# SCH_task3_2026-04-27.net
KiCad netlist of a schematic drawn in EasyEDA
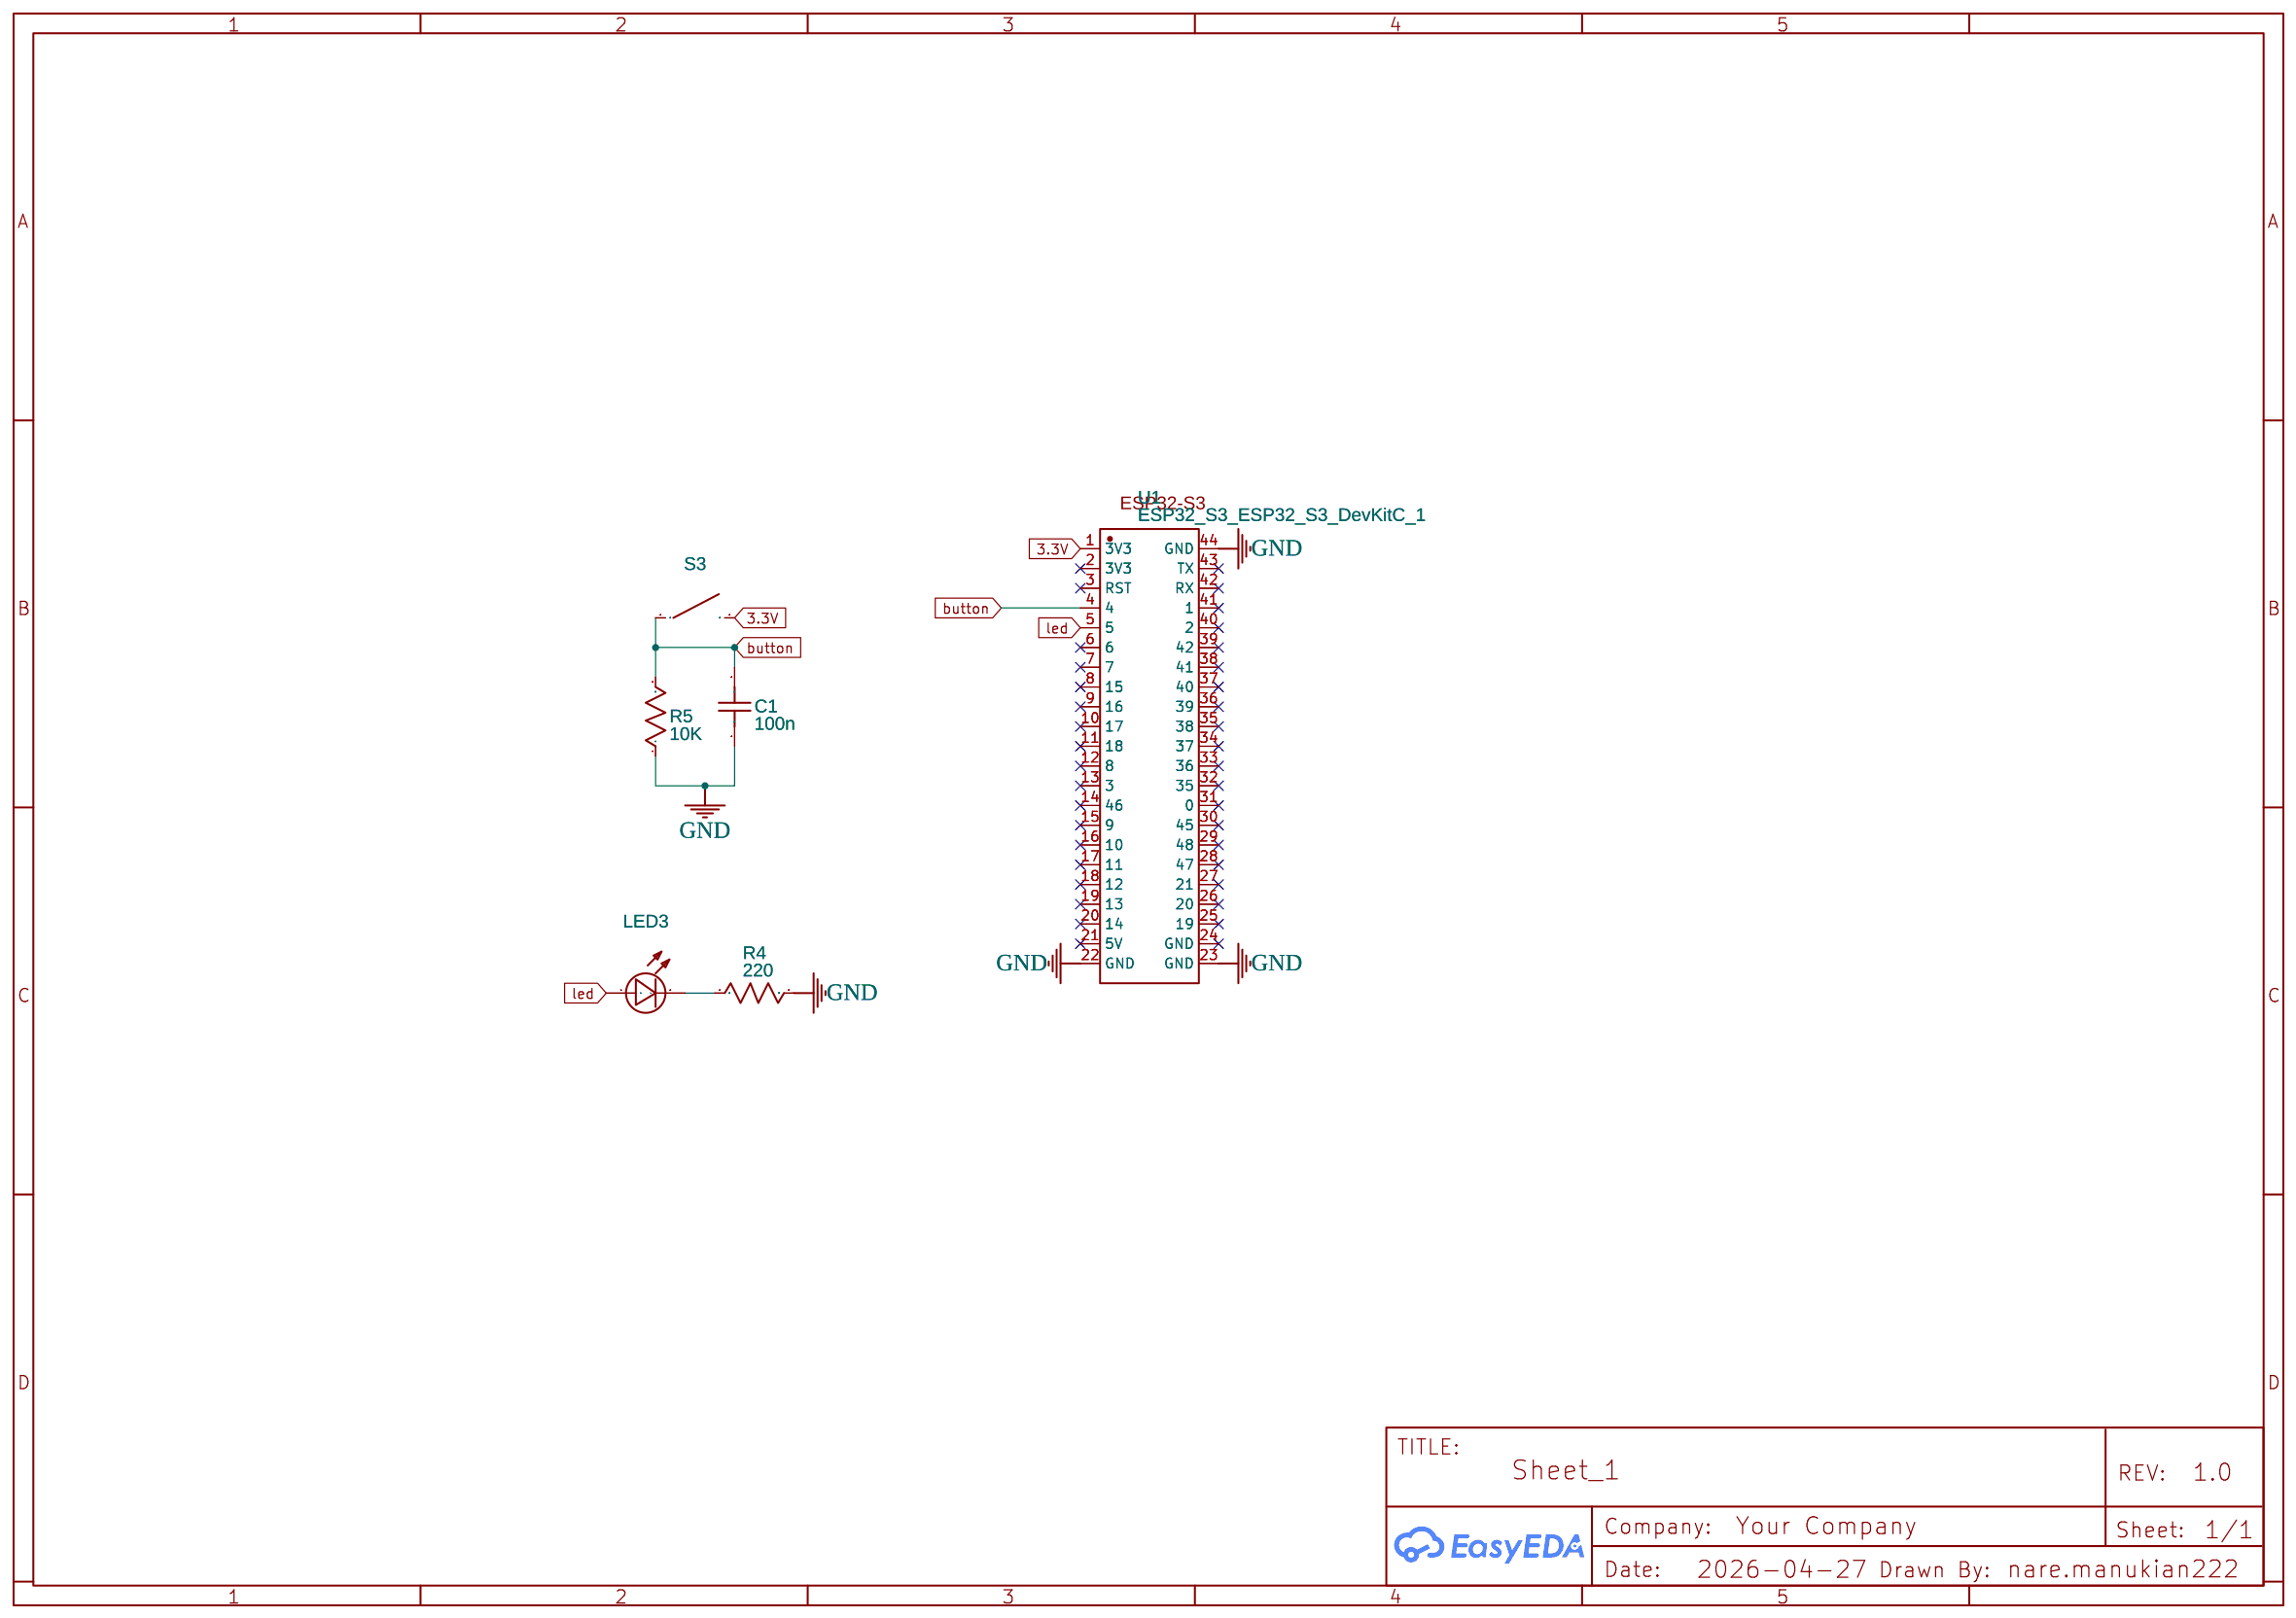
[diagram p0: schematic sheet]

(export (version "E")
  (design (tool "Eeschema 10.0.6"))
  (components
    (comp (ref "C1") (value "100n") (libsource (lib "") (part "Capacitor_US")))
    (comp (ref "LED3") (value "LED") (libsource (lib "") (part "LED")))
    (comp (ref "R4") (value "220") (libsource (lib "") (part "Resistor_US")))
    (comp (ref "R5") (value "10K") (libsource (lib "") (part "Resistor_US_1")))
    (comp (ref "S3") (value "SPST_Open") (libsource (lib "") (part "SPST")))
    (comp (ref "U1")
      (value "ESP32_S3_ESP32_S3_DevKitC_1")
      (fields (field (name "Manufacturer") "DUBEUYEW"))
      (libsource (lib "") (part "ESP32_S3_ESP32_S3_DevKitC_1"))
    )
  )
  (nets
    (net (code "1") (name "3.3V") (class "Default")
      (node (ref "S3") (pin "2") (pinfunction "2_2") (pintype "unspecified"))
      (node (ref "U1") (pin "1") (pinfunction "3V3_1") (pintype "unspecified"))
    )
    (net (code "2") (name "GND") (class "Default")
      (node (ref "C1") (pin "1") (pinfunction "1_1") (pintype "unspecified"))
      (node (ref "R4") (pin "2") (pinfunction "2_2") (pintype "unspecified"))
      (node (ref "R5") (pin "1") (pinfunction "1_1") (pintype "unspecified"))
      (node (ref "U1") (pin "22") (pinfunction "GND_22") (pintype "unspecified"))
      (node (ref "U1") (pin "23") (pinfunction "GND_23") (pintype "unspecified"))
      (node (ref "U1") (pin "44") (pinfunction "GND_44") (pintype "unspecified"))
    )
    (net (code "3") (name "Net-(LED3--)") (class "Default")
      (node (ref "LED3") (pin "2") (pinfunction "-_2") (pintype "unspecified"))
      (node (ref "R4") (pin "1") (pinfunction "1_1") (pintype "unspecified"))
    )
    (net (code "4") (name "button") (class "Default")
      (node (ref "C1") (pin "2") (pinfunction "2_2") (pintype "unspecified"))
      (node (ref "R5") (pin "2") (pinfunction "2_2") (pintype "unspecified"))
      (node (ref "S3") (pin "1") (pinfunction "1_1") (pintype "unspecified"))
      (node (ref "U1") (pin "4") (pinfunction "4_4") (pintype "unspecified"))
    )
    (net (code "5") (name "led") (class "Default")
      (node (ref "LED3") (pin "1") (pinfunction "+_1") (pintype "unspecified"))
      (node (ref "U1") (pin "5") (pinfunction "5_5") (pintype "unspecified"))
    )
    (net (code "6") (name "unconnected-(U1-0-Pad31)") (class "Default")
      (node (ref "U1") (pin "31") (pinfunction "0_31") (pintype "unspecified+no_connect"))
    )
    (net (code "7") (name "unconnected-(U1-1-Pad41)") (class "Default")
      (node (ref "U1") (pin "41") (pinfunction "1_41") (pintype "unspecified+no_connect"))
    )
    (net (code "8") (name "unconnected-(U1-2-Pad40)") (class "Default")
      (node (ref "U1") (pin "40") (pinfunction "2_40") (pintype "unspecified+no_connect"))
    )
    (net (code "9") (name "unconnected-(U1-3-Pad13)") (class "Default")
      (node (ref "U1") (pin "13") (pinfunction "3_13") (pintype "unspecified+no_connect"))
    )
    (net (code "10") (name "unconnected-(U1-3V3-Pad2)") (class "Default")
      (node (ref "U1") (pin "2") (pinfunction "3V3_2") (pintype "unspecified+no_connect"))
    )
    (net (code "11") (name "unconnected-(U1-5V-Pad21)") (class "Default")
      (node (ref "U1") (pin "21") (pinfunction "5V_21") (pintype "unspecified+no_connect"))
    )
    (net (code "12") (name "unconnected-(U1-8-Pad12)") (class "Default")
      (node (ref "U1") (pin "12") (pinfunction "8_12") (pintype "unspecified+no_connect"))
    )
    (net (code "13") (name "unconnected-(U1-9-Pad15)") (class "Default")
      (node (ref "U1") (pin "15") (pinfunction "9_15") (pintype "unspecified+no_connect"))
    )
    (net (code "14") (name "unconnected-(U1-10-Pad16)") (class "Default")
      (node (ref "U1") (pin "16") (pinfunction "10_16") (pintype "unspecified+no_connect"))
    )
    (net (code "15") (name "unconnected-(U1-11-Pad17)") (class "Default")
      (node (ref "U1") (pin "17") (pinfunction "11_17") (pintype "unspecified+no_connect"))
    )
    (net (code "16") (name "unconnected-(U1-12-Pad18)") (class "Default")
      (node (ref "U1") (pin "18") (pinfunction "12_18") (pintype "unspecified+no_connect"))
    )
    (net (code "17") (name "unconnected-(U1-13-Pad19)") (class "Default")
      (node (ref "U1") (pin "19") (pinfunction "13_19") (pintype "unspecified+no_connect"))
    )
    (net (code "18") (name "unconnected-(U1-14-Pad20)") (class "Default")
      (node (ref "U1") (pin "20") (pinfunction "14_20") (pintype "unspecified+no_connect"))
    )
    (net (code "19") (name "unconnected-(U1-15-Pad8)") (class "Default")
      (node (ref "U1") (pin "8") (pinfunction "15_8") (pintype "unspecified+no_connect"))
    )
    (net (code "20") (name "unconnected-(U1-16-Pad9)") (class "Default")
      (node (ref "U1") (pin "9") (pinfunction "16_9") (pintype "unspecified+no_connect"))
    )
    (net (code "21") (name "unconnected-(U1-17-Pad10)") (class "Default")
      (node (ref "U1") (pin "10") (pinfunction "17_10") (pintype "unspecified+no_connect"))
    )
    (net (code "22") (name "unconnected-(U1-18-Pad11)") (class "Default")
      (node (ref "U1") (pin "11") (pinfunction "18_11") (pintype "unspecified+no_connect"))
    )
    (net (code "23") (name "unconnected-(U1-19-Pad25)") (class "Default")
      (node (ref "U1") (pin "25") (pinfunction "19_25") (pintype "unspecified+no_connect"))
    )
    (net (code "24") (name "unconnected-(U1-20-Pad26)") (class "Default")
      (node (ref "U1") (pin "26") (pinfunction "20_26") (pintype "unspecified+no_connect"))
    )
    (net (code "25") (name "unconnected-(U1-21-Pad27)") (class "Default")
      (node (ref "U1") (pin "27") (pinfunction "21_27") (pintype "unspecified+no_connect"))
    )
    (net (code "26") (name "unconnected-(U1-35-Pad32)") (class "Default")
      (node (ref "U1") (pin "32") (pinfunction "35_32") (pintype "unspecified+no_connect"))
    )
    (net (code "27") (name "unconnected-(U1-36-Pad33)") (class "Default")
      (node (ref "U1") (pin "33") (pinfunction "36_33") (pintype "unspecified+no_connect"))
    )
    (net (code "28") (name "unconnected-(U1-37-Pad34)") (class "Default")
      (node (ref "U1") (pin "34") (pinfunction "37_34") (pintype "unspecified+no_connect"))
    )
    (net (code "29") (name "unconnected-(U1-38-Pad35)") (class "Default")
      (node (ref "U1") (pin "35") (pinfunction "38_35") (pintype "unspecified+no_connect"))
    )
    (net (code "30") (name "unconnected-(U1-39-Pad36)") (class "Default")
      (node (ref "U1") (pin "36") (pinfunction "39_36") (pintype "unspecified+no_connect"))
    )
    (net (code "31") (name "unconnected-(U1-40-Pad37)") (class "Default")
      (node (ref "U1") (pin "37") (pinfunction "40_37") (pintype "unspecified+no_connect"))
    )
    (net (code "32") (name "unconnected-(U1-41-Pad38)") (class "Default")
      (node (ref "U1") (pin "38") (pinfunction "41_38") (pintype "unspecified+no_connect"))
    )
    (net (code "33") (name "unconnected-(U1-42-Pad39)") (class "Default")
      (node (ref "U1") (pin "39") (pinfunction "42_39") (pintype "unspecified+no_connect"))
    )
    (net (code "34") (name "unconnected-(U1-45-Pad30)") (class "Default")
      (node (ref "U1") (pin "30") (pinfunction "45_30") (pintype "unspecified+no_connect"))
    )
    (net (code "35") (name "unconnected-(U1-46-Pad14)") (class "Default")
      (node (ref "U1") (pin "14") (pinfunction "46_14") (pintype "unspecified+no_connect"))
    )
    (net (code "36") (name "unconnected-(U1-47-Pad28)") (class "Default")
      (node (ref "U1") (pin "28") (pinfunction "47_28") (pintype "unspecified+no_connect"))
    )
    (net (code "37") (name "unconnected-(U1-48-Pad29)") (class "Default")
      (node (ref "U1") (pin "29") (pinfunction "48_29") (pintype "unspecified+no_connect"))
    )
    (net (code "38") (name "unconnected-(U1-GND-Pad24)") (class "Default")
      (node (ref "U1") (pin "24") (pinfunction "GND_24") (pintype "unspecified+no_connect"))
    )
    (net (code "39") (name "unconnected-(U1-Pad6)") (class "Default")
      (node (ref "U1") (pin "6") (pinfunction "6_6") (pintype "unspecified+no_connect"))
    )
    (net (code "40") (name "unconnected-(U1-Pad7)") (class "Default")
      (node (ref "U1") (pin "7") (pinfunction "7_7") (pintype "unspecified+no_connect"))
    )
    (net (code "41") (name "unconnected-(U1-RST-Pad3)") (class "Default")
      (node (ref "U1") (pin "3") (pinfunction "RST_3") (pintype "unspecified+no_connect"))
    )
    (net (code "42") (name "unconnected-(U1-RX-Pad42)") (class "Default")
      (node (ref "U1") (pin "42") (pinfunction "RX_42") (pintype "unspecified+no_connect"))
    )
    (net (code "43") (name "unconnected-(U1-TX-Pad43)") (class "Default")
      (node (ref "U1") (pin "43") (pinfunction "TX_43") (pintype "unspecified+no_connect"))
    )
  )
)
